# Sheet1.net
KiCad netlist of a schematic drawn in Altium Designer
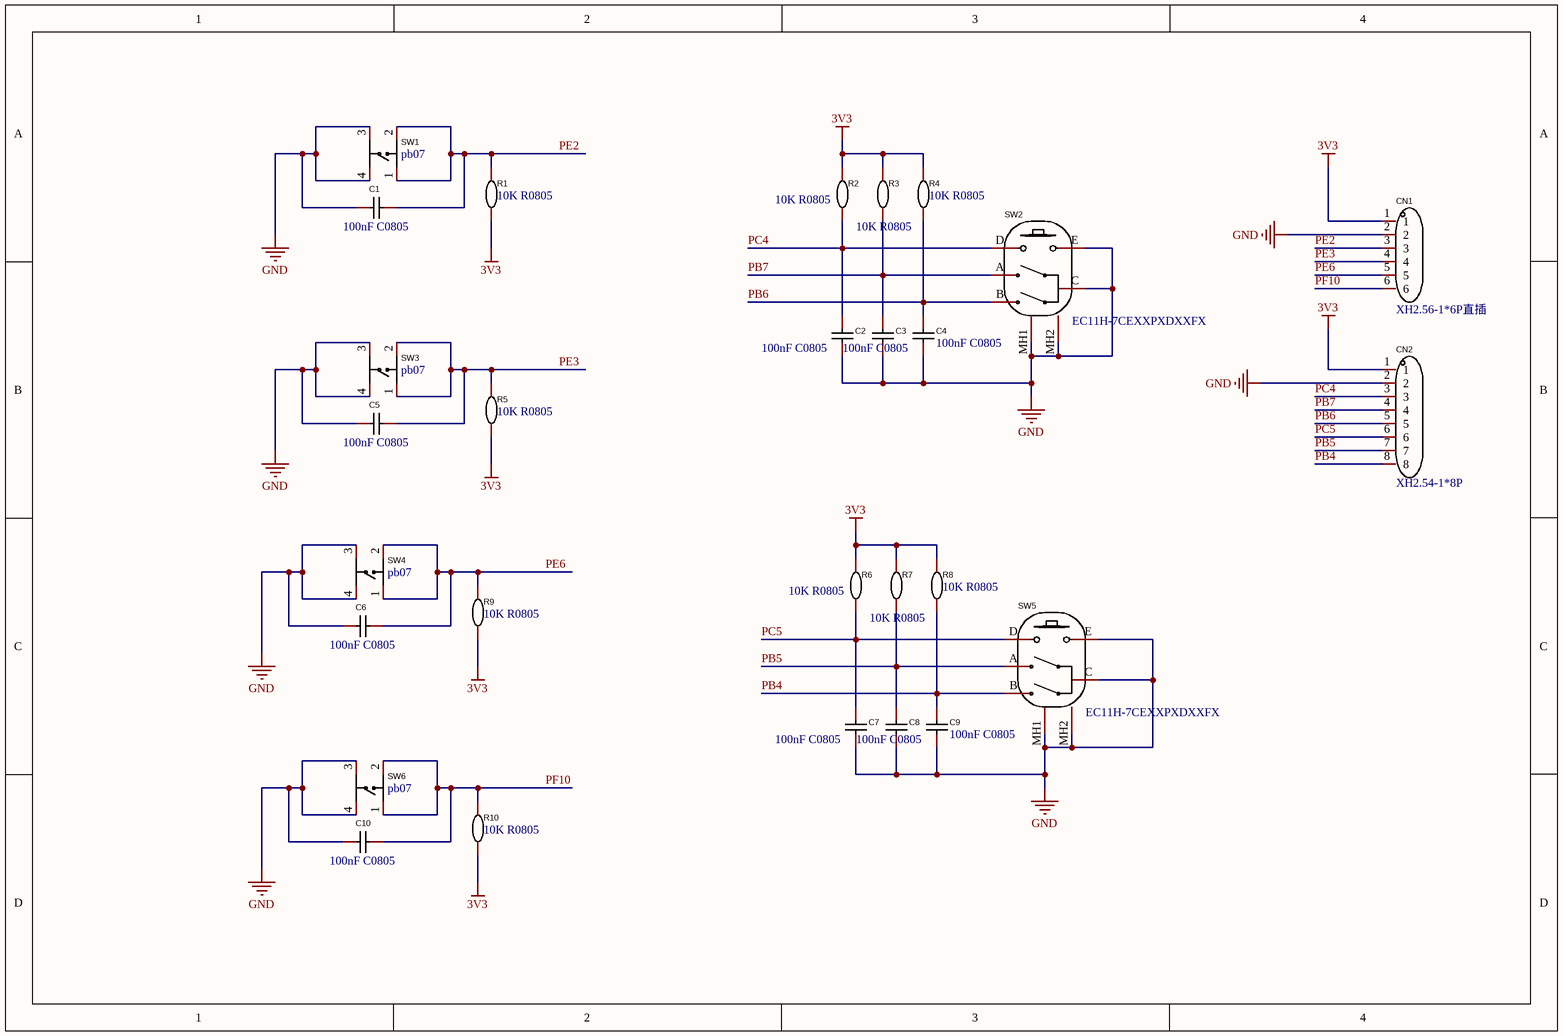
[diagram p0: Sheet1.SchDoc]

(export (version "E")
  (design (tool "Eeschema 10.0.6"))
  (components
    (comp (ref "C1")
      (value "100nF C0805")
      (footprint "C0805")
      (fields
        (field (name "MANUFACTURER") "SAMSUNG(三星)")
        (field (name "MANUFACTURER PART") "CL21A106KAYNNNE")
        (field (name "TOLERANCE") "±10%")
      )
      (libsource (lib "Schlib1") (part "C0805"))
    )
    (comp (ref "C2")
      (value "100nF C0805")
      (footprint "C0805")
      (fields
        (field (name "MANUFACTURER") "SAMSUNG(三星)")
        (field (name "MANUFACTURER PART") "CL21A106KAYNNNE")
        (field (name "TOLERANCE") "±10%")
      )
      (libsource (lib "Schlib1") (part "C0805"))
    )
    (comp (ref "C3")
      (value "100nF C0805")
      (footprint "C0805")
      (fields
        (field (name "MANUFACTURER") "SAMSUNG(三星)")
        (field (name "MANUFACTURER PART") "CL21A106KAYNNNE")
        (field (name "TOLERANCE") "±10%")
      )
      (libsource (lib "Schlib1") (part "C0805"))
    )
    (comp (ref "C4")
      (value "100nF C0805")
      (footprint "C0805")
      (fields
        (field (name "MANUFACTURER") "SAMSUNG(三星)")
        (field (name "MANUFACTURER PART") "CL21A106KAYNNNE")
        (field (name "TOLERANCE") "±10%")
      )
      (libsource (lib "Schlib1") (part "C0805"))
    )
    (comp (ref "C5")
      (value "100nF C0805")
      (footprint "C0805")
      (fields
        (field (name "MANUFACTURER") "SAMSUNG(三星)")
        (field (name "MANUFACTURER PART") "CL21A106KAYNNNE")
        (field (name "TOLERANCE") "±10%")
      )
      (libsource (lib "Schlib1") (part "C0805"))
    )
    (comp (ref "C6")
      (value "100nF C0805")
      (footprint "C0805")
      (fields
        (field (name "MANUFACTURER") "SAMSUNG(三星)")
        (field (name "MANUFACTURER PART") "CL21A106KAYNNNE")
        (field (name "TOLERANCE") "±10%")
      )
      (libsource (lib "Schlib1") (part "C0805"))
    )
    (comp (ref "C7")
      (value "100nF C0805")
      (footprint "C0805")
      (fields
        (field (name "MANUFACTURER") "SAMSUNG(三星)")
        (field (name "MANUFACTURER PART") "CL21A106KAYNNNE")
        (field (name "TOLERANCE") "±10%")
      )
      (libsource (lib "Schlib1") (part "C0805"))
    )
    (comp (ref "C8")
      (value "100nF C0805")
      (footprint "C0805")
      (fields
        (field (name "MANUFACTURER") "SAMSUNG(三星)")
        (field (name "MANUFACTURER PART") "CL21A106KAYNNNE")
        (field (name "TOLERANCE") "±10%")
      )
      (libsource (lib "Schlib1") (part "C0805"))
    )
    (comp (ref "C9")
      (value "100nF C0805")
      (footprint "C0805")
      (fields
        (field (name "MANUFACTURER") "SAMSUNG(三星)")
        (field (name "MANUFACTURER PART") "CL21A106KAYNNNE")
        (field (name "TOLERANCE") "±10%")
      )
      (libsource (lib "Schlib1") (part "C0805"))
    )
    (comp (ref "C10")
      (value "100nF C0805")
      (footprint "C0805")
      (fields
        (field (name "MANUFACTURER") "SAMSUNG(三星)")
        (field (name "MANUFACTURER PART") "CL21A106KAYNNNE")
        (field (name "TOLERANCE") "±10%")
      )
      (libsource (lib "Schlib1") (part "C0805"))
    )
    (comp (ref "CN1")
      (value "XH2.56-1*6P直插")
      (footprint "H2.54-1*6P-直插CONN-TH_6P-P2.50_HC-XH-6A-G")
      (fields (field (name "MANUFACTURER") "HCTL(华灿天禄)") (field (name "MANUFACTURER PART") "HC-XH-6AW-G"))
      (libsource (lib "Schlib1") (part "XH2.56-1*6P直插"))
    )
    (comp (ref "CN2")
      (value "XH2.54-1*8P")
      (footprint "XH2.54-1*8P-CONN-TH_8P-P2.50_HC-XH-8A-G")
      (description "XH2.54-1*8P//直插//C5341207")
      (fields (field (name "MANUFACTURER") "HCTL(华灿天禄)") (field (name "MANUFACTURER PART") "HC-XH-8A-G"))
      (libsource (lib "Schlib1") (part "XH2.54-1*8P"))
    )
    (comp (ref "R1")
      (value "10K R0805")
      (footprint "R0805")
      (fields
        (field (name "MANUFACTURER") "UNI-ROYAL(厚声)")
        (field (name "MANUFACTURER PART") "0805W8F1002T5E")
        (field (name "TOLERANCE") "±1%")
      )
      (libsource (lib "Schlib1") (part "R0805"))
    )
    (comp (ref "R2")
      (value "10K R0805")
      (footprint "R0805")
      (fields
        (field (name "MANUFACTURER") "UNI-ROYAL(厚声)")
        (field (name "MANUFACTURER PART") "0805W8F1002T5E")
        (field (name "TOLERANCE") "±1%")
      )
      (libsource (lib "Schlib1") (part "R0805"))
    )
    (comp (ref "R3")
      (value "10K R0805")
      (footprint "R0805")
      (fields
        (field (name "MANUFACTURER") "UNI-ROYAL(厚声)")
        (field (name "MANUFACTURER PART") "0805W8F1002T5E")
        (field (name "TOLERANCE") "±1%")
      )
      (libsource (lib "Schlib1") (part "R0805"))
    )
    (comp (ref "R4")
      (value "10K R0805")
      (footprint "R0805")
      (fields
        (field (name "MANUFACTURER") "UNI-ROYAL(厚声)")
        (field (name "MANUFACTURER PART") "0805W8F1002T5E")
        (field (name "TOLERANCE") "±1%")
      )
      (libsource (lib "Schlib1") (part "R0805"))
    )
    (comp (ref "R5")
      (value "10K R0805")
      (footprint "R0805")
      (fields
        (field (name "MANUFACTURER") "UNI-ROYAL(厚声)")
        (field (name "MANUFACTURER PART") "0805W8F1002T5E")
        (field (name "TOLERANCE") "±1%")
      )
      (libsource (lib "Schlib1") (part "R0805"))
    )
    (comp (ref "R6")
      (value "10K R0805")
      (footprint "R0805")
      (fields
        (field (name "MANUFACTURER") "UNI-ROYAL(厚声)")
        (field (name "MANUFACTURER PART") "0805W8F1002T5E")
        (field (name "TOLERANCE") "±1%")
      )
      (libsource (lib "Schlib1") (part "R0805"))
    )
    (comp (ref "R7")
      (value "10K R0805")
      (footprint "R0805")
      (fields
        (field (name "MANUFACTURER") "UNI-ROYAL(厚声)")
        (field (name "MANUFACTURER PART") "0805W8F1002T5E")
        (field (name "TOLERANCE") "±1%")
      )
      (libsource (lib "Schlib1") (part "R0805"))
    )
    (comp (ref "R8")
      (value "10K R0805")
      (footprint "R0805")
      (fields
        (field (name "MANUFACTURER") "UNI-ROYAL(厚声)")
        (field (name "MANUFACTURER PART") "0805W8F1002T5E")
        (field (name "TOLERANCE") "±1%")
      )
      (libsource (lib "Schlib1") (part "R0805"))
    )
    (comp (ref "R9")
      (value "10K R0805")
      (footprint "R0805")
      (fields
        (field (name "MANUFACTURER") "UNI-ROYAL(厚声)")
        (field (name "MANUFACTURER PART") "0805W8F1002T5E")
        (field (name "TOLERANCE") "±1%")
      )
      (libsource (lib "Schlib1") (part "R0805"))
    )
    (comp (ref "R10")
      (value "10K R0805")
      (footprint "R0805")
      (fields
        (field (name "MANUFACTURER") "UNI-ROYAL(厚声)")
        (field (name "MANUFACTURER PART") "0805W8F1002T5E")
        (field (name "TOLERANCE") "±1%")
      )
      (libsource (lib "Schlib1") (part "R0805"))
    )
    (comp (ref "SW1")
      (value "pb07")
      (footprint "KEY-pb07-5.08*5.08")
      (description "pb07无声轻触按键//东莞市荣硕电子")
      (fields
        (field (name "MANUFACTURER") "Yuandi(元迪)")
        (field (name "MANUFACTURER PART") "TS-1095PD-A9B3-D2")
      )
      (libsource (lib "Schlib1") (part "pb07"))
    )
    (comp (ref "SW2")
      (value "EC11H-7CEXXPXDXXFX")
      (footprint "旋转编码器-有焊盘修改SW-TH_EC11K1524406")
      (description "EC11H-7CEXXPXDXXFX//宏彦科技")
      (fields
        (field (name "MANUFACTURER") "ALPSALPINE(阿尔卑斯阿尔派)")
        (field (name "MANUFACTURER PART") "EC11K1524406")
      )
      (libsource (lib "Schlib1") (part "EC11H-7CEXXPXDXXFX"))
    )
    (comp (ref "SW3")
      (value "pb07")
      (footprint "KEY-pb07-5.08*5.08")
      (description "pb07无声轻触按键//东莞市荣硕电子")
      (fields
        (field (name "MANUFACTURER") "Yuandi(元迪)")
        (field (name "MANUFACTURER PART") "TS-1095PD-A9B3-D2")
      )
      (libsource (lib "Schlib1") (part "pb07"))
    )
    (comp (ref "SW4")
      (value "pb07")
      (footprint "KEY-pb07-5.08*5.08")
      (description "pb07无声轻触按键//东莞市荣硕电子")
      (fields
        (field (name "MANUFACTURER") "Yuandi(元迪)")
        (field (name "MANUFACTURER PART") "TS-1095PD-A9B3-D2")
      )
      (libsource (lib "Schlib1") (part "pb07"))
    )
    (comp (ref "SW5")
      (value "EC11H-7CEXXPXDXXFX")
      (footprint "旋转编码器-有焊盘修改SW-TH_EC11K1524406")
      (description "EC11H-7CEXXPXDXXFX//宏彦科技")
      (fields
        (field (name "MANUFACTURER") "ALPSALPINE(阿尔卑斯阿尔派)")
        (field (name "MANUFACTURER PART") "EC11K1524406")
      )
      (libsource (lib "Schlib1") (part "EC11H-7CEXXPXDXXFX"))
    )
    (comp (ref "SW6")
      (value "pb07")
      (footprint "KEY-pb07-5.08*5.08")
      (description "pb07无声轻触按键//东莞市荣硕电子")
      (fields
        (field (name "MANUFACTURER") "Yuandi(元迪)")
        (field (name "MANUFACTURER PART") "TS-1095PD-A9B3-D2")
      )
      (libsource (lib "Schlib1") (part "pb07"))
    )
  )
  (nets
    (net (code "1") (name "/PB4") (class "Default")
      (node (ref "C9") (pin "2") (pinfunction "2_2") (pintype "passive"))
      (node (ref "CN2") (pin "8") (pinfunction "8_8") (pintype "passive"))
      (node (ref "R8") (pin "1") (pinfunction "1_1") (pintype "passive"))
      (node (ref "SW5") (pin "B") (pinfunction "B_B") (pintype "passive"))
    )
    (net (code "2") (name "/PB5") (class "Default")
      (node (ref "C8") (pin "2") (pinfunction "2_2") (pintype "passive"))
      (node (ref "CN2") (pin "7") (pinfunction "7_7") (pintype "passive"))
      (node (ref "R7") (pin "1") (pinfunction "1_1") (pintype "passive"))
      (node (ref "SW5") (pin "A") (pinfunction "A_A") (pintype "passive"))
    )
    (net (code "3") (name "/PB6") (class "Default")
      (node (ref "C4") (pin "2") (pinfunction "2_2") (pintype "passive"))
      (node (ref "CN2") (pin "5") (pinfunction "5_5") (pintype "passive"))
      (node (ref "R4") (pin "1") (pinfunction "1_1") (pintype "passive"))
      (node (ref "SW2") (pin "B") (pinfunction "B_B") (pintype "passive"))
    )
    (net (code "4") (name "/PB7") (class "Default")
      (node (ref "C3") (pin "2") (pinfunction "2_2") (pintype "passive"))
      (node (ref "CN2") (pin "4") (pinfunction "4_4") (pintype "passive"))
      (node (ref "R3") (pin "1") (pinfunction "1_1") (pintype "passive"))
      (node (ref "SW2") (pin "A") (pinfunction "A_A") (pintype "passive"))
    )
    (net (code "5") (name "/PC4") (class "Default")
      (node (ref "C2") (pin "2") (pinfunction "2_2") (pintype "passive"))
      (node (ref "CN2") (pin "3") (pinfunction "3_3") (pintype "passive"))
      (node (ref "R2") (pin "1") (pinfunction "1_1") (pintype "passive"))
      (node (ref "SW2") (pin "D") (pinfunction "D_D") (pintype "passive"))
    )
    (net (code "6") (name "/PC5") (class "Default")
      (node (ref "C7") (pin "2") (pinfunction "2_2") (pintype "passive"))
      (node (ref "CN2") (pin "6") (pinfunction "6_6") (pintype "passive"))
      (node (ref "R6") (pin "1") (pinfunction "1_1") (pintype "passive"))
      (node (ref "SW5") (pin "D") (pinfunction "D_D") (pintype "passive"))
    )
    (net (code "7") (name "/PE2") (class "Default")
      (node (ref "C1") (pin "2") (pinfunction "2_2") (pintype "passive"))
      (node (ref "CN1") (pin "3") (pinfunction "3_3") (pintype "passive"))
      (node (ref "R1") (pin "2") (pinfunction "2_2") (pintype "passive"))
      (node (ref "SW1") (pin "1") (pinfunction "1_1") (pintype "passive"))
      (node (ref "SW1") (pin "2") (pinfunction "2_2") (pintype "passive"))
    )
    (net (code "8") (name "/PE3") (class "Default")
      (node (ref "C5") (pin "2") (pinfunction "2_2") (pintype "passive"))
      (node (ref "CN1") (pin "4") (pinfunction "4_4") (pintype "passive"))
      (node (ref "R5") (pin "2") (pinfunction "2_2") (pintype "passive"))
      (node (ref "SW3") (pin "1") (pinfunction "1_1") (pintype "passive"))
      (node (ref "SW3") (pin "2") (pinfunction "2_2") (pintype "passive"))
    )
    (net (code "9") (name "/PE6") (class "Default")
      (node (ref "C6") (pin "2") (pinfunction "2_2") (pintype "passive"))
      (node (ref "CN1") (pin "5") (pinfunction "5_5") (pintype "passive"))
      (node (ref "R9") (pin "2") (pinfunction "2_2") (pintype "passive"))
      (node (ref "SW4") (pin "1") (pinfunction "1_1") (pintype "passive"))
      (node (ref "SW4") (pin "2") (pinfunction "2_2") (pintype "passive"))
    )
    (net (code "10") (name "/PF10") (class "Default")
      (node (ref "C10") (pin "2") (pinfunction "2_2") (pintype "passive"))
      (node (ref "CN1") (pin "6") (pinfunction "6_6") (pintype "passive"))
      (node (ref "R10") (pin "2") (pinfunction "2_2") (pintype "passive"))
      (node (ref "SW6") (pin "1") (pinfunction "1_1") (pintype "passive"))
      (node (ref "SW6") (pin "2") (pinfunction "2_2") (pintype "passive"))
    )
    (net (code "11") (name "3V3") (class "Default")
      (node (ref "CN1") (pin "1") (pinfunction "1_1") (pintype "passive"))
      (node (ref "CN2") (pin "1") (pinfunction "1_1") (pintype "passive"))
      (node (ref "R1") (pin "1") (pinfunction "1_1") (pintype "passive"))
      (node (ref "R10") (pin "1") (pinfunction "1_1") (pintype "passive"))
      (node (ref "R2") (pin "2") (pinfunction "2_2") (pintype "passive"))
      (node (ref "R3") (pin "2") (pinfunction "2_2") (pintype "passive"))
      (node (ref "R4") (pin "2") (pinfunction "2_2") (pintype "passive"))
      (node (ref "R5") (pin "1") (pinfunction "1_1") (pintype "passive"))
      (node (ref "R6") (pin "2") (pinfunction "2_2") (pintype "passive"))
      (node (ref "R7") (pin "2") (pinfunction "2_2") (pintype "passive"))
      (node (ref "R8") (pin "2") (pinfunction "2_2") (pintype "passive"))
      (node (ref "R9") (pin "1") (pinfunction "1_1") (pintype "passive"))
    )
    (net (code "12") (name "GND") (class "Default")
      (node (ref "C1") (pin "1") (pinfunction "1_1") (pintype "passive"))
      (node (ref "C10") (pin "1") (pinfunction "1_1") (pintype "passive"))
      (node (ref "C2") (pin "1") (pinfunction "1_1") (pintype "passive"))
      (node (ref "C3") (pin "1") (pinfunction "1_1") (pintype "passive"))
      (node (ref "C4") (pin "1") (pinfunction "1_1") (pintype "passive"))
      (node (ref "C5") (pin "1") (pinfunction "1_1") (pintype "passive"))
      (node (ref "C6") (pin "1") (pinfunction "1_1") (pintype "passive"))
      (node (ref "C7") (pin "1") (pinfunction "1_1") (pintype "passive"))
      (node (ref "C8") (pin "1") (pinfunction "1_1") (pintype "passive"))
      (node (ref "C9") (pin "1") (pinfunction "1_1") (pintype "passive"))
      (node (ref "CN1") (pin "2") (pinfunction "2_2") (pintype "passive"))
      (node (ref "CN2") (pin "2") (pinfunction "2_2") (pintype "passive"))
      (node (ref "SW1") (pin "3") (pinfunction "3_3") (pintype "passive"))
      (node (ref "SW1") (pin "4") (pinfunction "4_4") (pintype "passive"))
      (node (ref "SW2") (pin "C") (pinfunction "C_C") (pintype "passive"))
      (node (ref "SW2") (pin "E") (pinfunction "E_E") (pintype "passive"))
      (node (ref "SW2") (pin "MH1") (pinfunction "MH1_MH1") (pintype "passive"))
      (node (ref "SW2") (pin "MH2") (pinfunction "MH2_MH2") (pintype "passive"))
      (node (ref "SW3") (pin "3") (pinfunction "3_3") (pintype "passive"))
      (node (ref "SW3") (pin "4") (pinfunction "4_4") (pintype "passive"))
      (node (ref "SW4") (pin "3") (pinfunction "3_3") (pintype "passive"))
      (node (ref "SW4") (pin "4") (pinfunction "4_4") (pintype "passive"))
      (node (ref "SW5") (pin "C") (pinfunction "C_C") (pintype "passive"))
      (node (ref "SW5") (pin "E") (pinfunction "E_E") (pintype "passive"))
      (node (ref "SW5") (pin "MH1") (pinfunction "MH1_MH1") (pintype "passive"))
      (node (ref "SW5") (pin "MH2") (pinfunction "MH2_MH2") (pintype "passive"))
      (node (ref "SW6") (pin "3") (pinfunction "3_3") (pintype "passive"))
      (node (ref "SW6") (pin "4") (pinfunction "4_4") (pintype "passive"))
    )
  )
)
